# Motors.net
KiCad netlist of a schematic drawn in Altium Designer
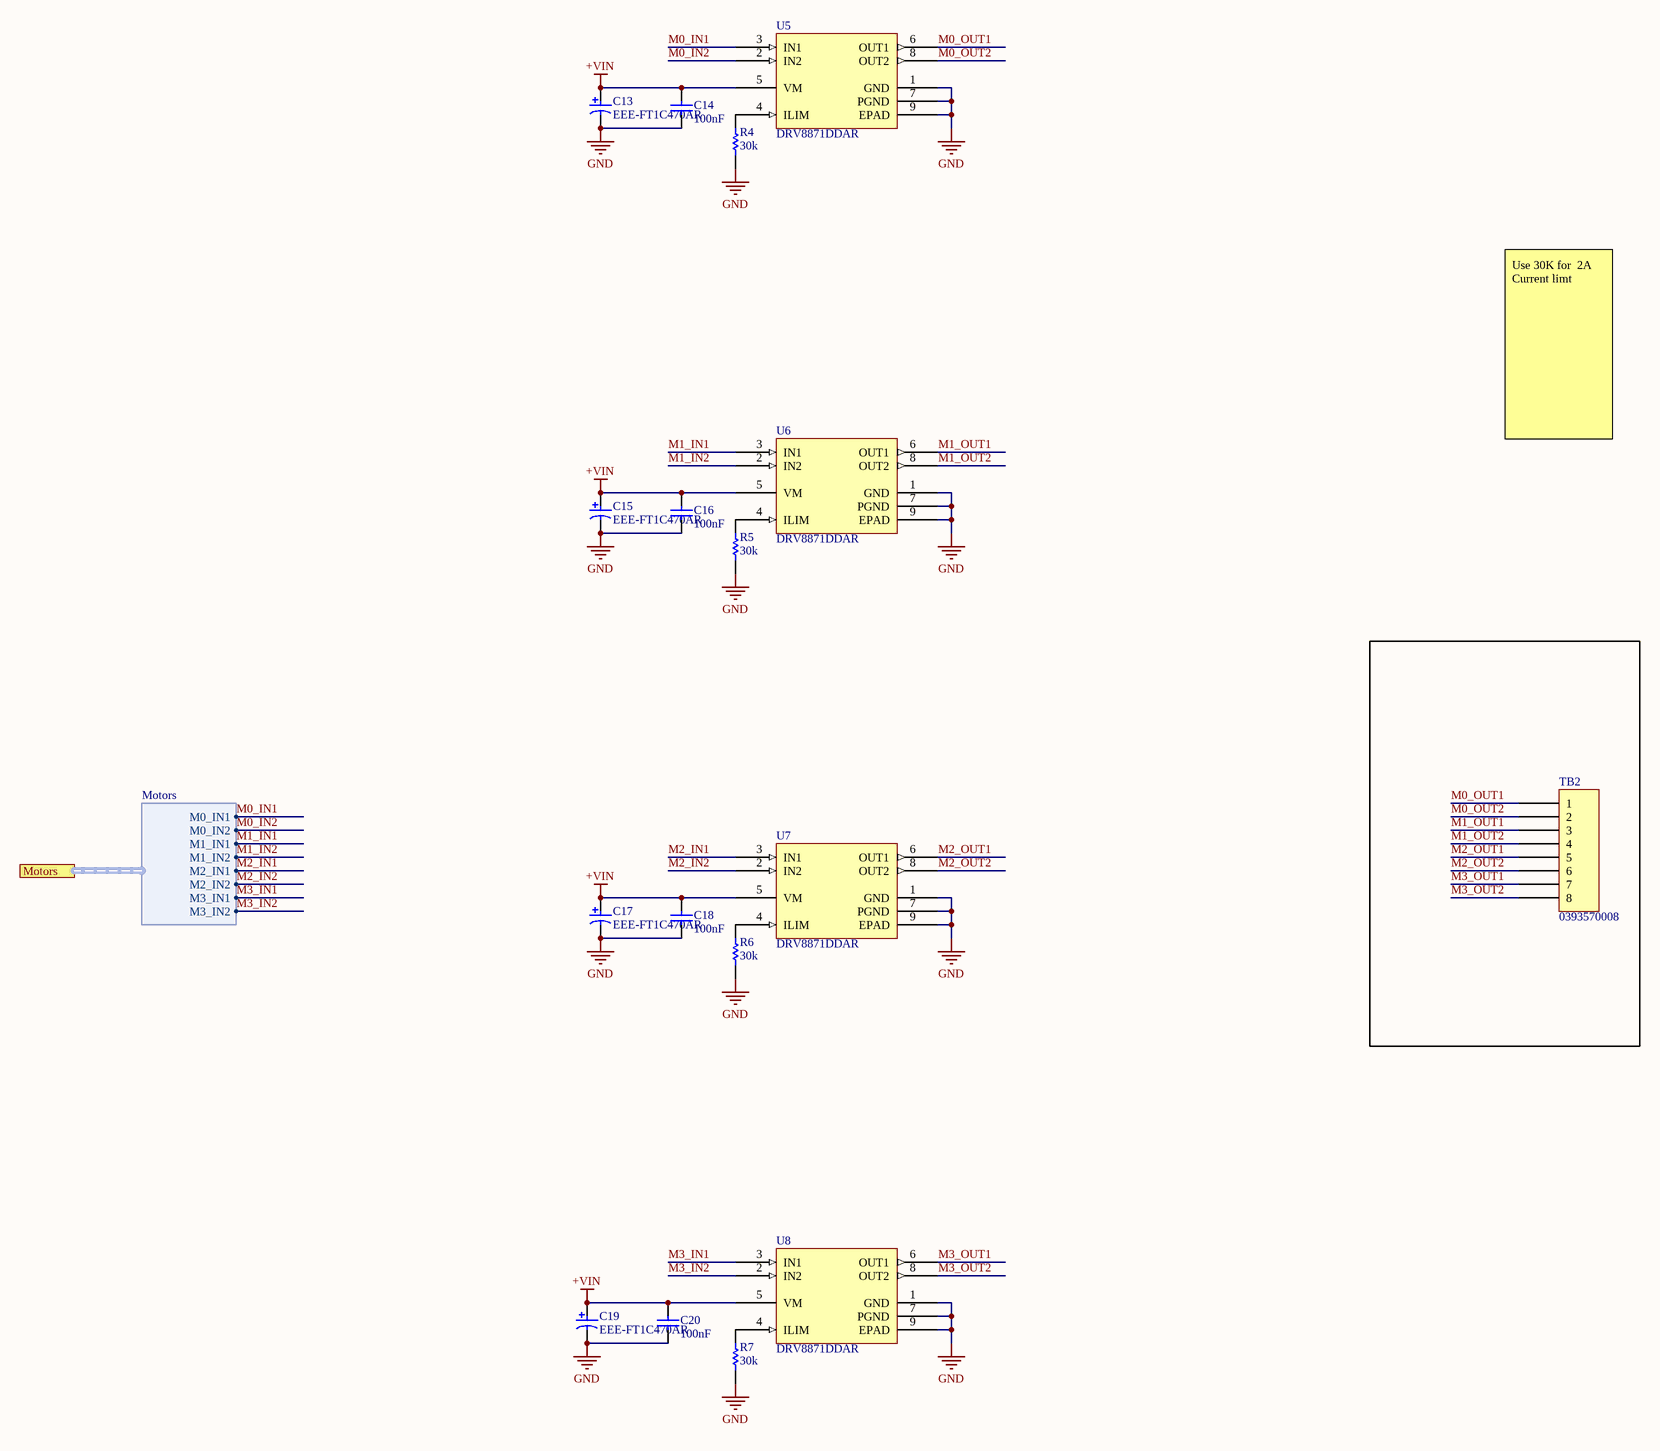
[diagram p0: Motors.SchDoc]

(export (version "E")
  (design (tool "Eeschema 10.0.6"))
  (components
    (comp (ref "C13")
      (value "EEE-FT1C470AR")
      (footprint "EEE-FT1C470AR")
      (fields
        (field (name "MANUFACTURER") "Panasonic")
        (field (name "MANUFACTURER PART NUMBER") "EEEFT1C470AR")
        (field (name "VOLTAGE") "16V")
      )
      (libsource (lib "altium-library") (part "EEE-FT1C470AR"))
    )
    (comp (ref "C14")
      (value "100nF")
      (footprint "0402")
      (description "TDK - C1005X7R1C104K050BC. - CERAMIC CAPACITOR, 0.1UF, 16V, X7R, 10%, 0402, FULL REEL")
      (fields
        (field (name "MANUFACTURER") "TDK")
        (field (name "MANUFACTURER PART NUMBER") "C1005X7R1C104K050BC")
      )
      (libsource (lib "altium-library") (part "Capacitor"))
    )
    (comp (ref "C15")
      (value "EEE-FT1C470AR")
      (footprint "EEE-FT1C470AR")
      (fields
        (field (name "MANUFACTURER") "Panasonic")
        (field (name "MANUFACTURER PART NUMBER") "EEEFT1C470AR")
        (field (name "VOLTAGE") "16V")
      )
      (libsource (lib "altium-library") (part "EEE-FT1C470AR"))
    )
    (comp (ref "C16")
      (value "100nF")
      (footprint "0402")
      (description "TDK - C1005X7R1C104K050BC. - CERAMIC CAPACITOR, 0.1UF, 16V, X7R, 10%, 0402, FULL REEL")
      (fields
        (field (name "MANUFACTURER") "TDK")
        (field (name "MANUFACTURER PART NUMBER") "C1005X7R1C104K050BC")
      )
      (libsource (lib "altium-library") (part "Capacitor"))
    )
    (comp (ref "C17")
      (value "EEE-FT1C470AR")
      (footprint "EEE-FT1C470AR")
      (fields
        (field (name "MANUFACTURER") "Panasonic")
        (field (name "MANUFACTURER PART NUMBER") "EEEFT1C470AR")
        (field (name "VOLTAGE") "16V")
      )
      (libsource (lib "altium-library") (part "EEE-FT1C470AR"))
    )
    (comp (ref "C18")
      (value "100nF")
      (footprint "0402")
      (description "TDK - C1005X7R1C104K050BC. - CERAMIC CAPACITOR, 0.1UF, 16V, X7R, 10%, 0402, FULL REEL")
      (fields
        (field (name "MANUFACTURER") "TDK")
        (field (name "MANUFACTURER PART NUMBER") "C1005X7R1C104K050BC")
      )
      (libsource (lib "altium-library") (part "Capacitor"))
    )
    (comp (ref "C19")
      (value "EEE-FT1C470AR")
      (footprint "EEE-FT1C470AR")
      (fields
        (field (name "MANUFACTURER") "Panasonic")
        (field (name "MANUFACTURER PART NUMBER") "EEEFT1C470AR")
        (field (name "VOLTAGE") "16V")
      )
      (libsource (lib "altium-library") (part "EEE-FT1C470AR"))
    )
    (comp (ref "C20")
      (value "100nF")
      (footprint "0402")
      (description "TDK - C1005X7R1C104K050BC. - CERAMIC CAPACITOR, 0.1UF, 16V, X7R, 10%, 0402, FULL REEL")
      (fields
        (field (name "MANUFACTURER") "TDK")
        (field (name "MANUFACTURER PART NUMBER") "C1005X7R1C104K050BC")
      )
      (libsource (lib "altium-library") (part "Capacitor"))
    )
    (comp (ref "R4")
      (value "30k")
      (footprint "0402")
      (description "Res Thick Film 0402 30K Ohm 1% 0.063W(1/16W) ±100ppm/C Molded SMD Automotive Paper T/R")
      (fields
        (field (name "MANUFACTURER") "Vishay")
        (field (name "MANUFACTURER PART NUMBER") "CRCW040230K0FKED")
      )
      (libsource (lib "altium-library") (part "Resistor"))
    )
    (comp (ref "R5")
      (value "30k")
      (footprint "0402")
      (description "Res Thick Film 0402 30K Ohm 1% 0.063W(1/16W) ±100ppm/C Molded SMD Automotive Paper T/R")
      (fields
        (field (name "MANUFACTURER") "Vishay")
        (field (name "MANUFACTURER PART NUMBER") "CRCW040230K0FKED")
      )
      (libsource (lib "altium-library") (part "Resistor"))
    )
    (comp (ref "R6")
      (value "30k")
      (footprint "0402")
      (description "Res Thick Film 0402 30K Ohm 1% 0.063W(1/16W) ±100ppm/C Molded SMD Automotive Paper T/R")
      (fields
        (field (name "MANUFACTURER") "Vishay")
        (field (name "MANUFACTURER PART NUMBER") "CRCW040230K0FKED")
      )
      (libsource (lib "altium-library") (part "Resistor"))
    )
    (comp (ref "R7")
      (value "30k")
      (footprint "0402")
      (description "Res Thick Film 0402 30K Ohm 1% 0.063W(1/16W) ±100ppm/C Molded SMD Automotive Paper T/R")
      (fields
        (field (name "MANUFACTURER") "Vishay")
        (field (name "MANUFACTURER PART NUMBER") "CRCW040230K0FKED")
      )
      (libsource (lib "altium-library") (part "Resistor"))
    )
    (comp (ref "TB2")
      (value "0393570008")
      (footprint "0393570008")
      (description "Conn Eurostyle Block 8 POS 3.5mm Solder ST Thru-Hole 17.5A/Contact")
      (fields (field (name "MANUFACTURER") "Molex") (field (name "VOLTAGE") "300V"))
      (libsource (lib "altium-library") (part "0393570008"))
    )
    (comp (ref "U5")
      (value "DRV8871DDAR")
      (footprint "8-HSOP")
      (description "IC BRUSHED DC MOTOR 8SOIC")
      (fields (field (name "MANUFACTURER") "Texas Instruments"))
      (libsource (lib "altium-library") (part "DRV8871DDAR"))
    )
    (comp (ref "U6")
      (value "DRV8871DDAR")
      (footprint "8-HSOP")
      (description "IC BRUSHED DC MOTOR 8SOIC")
      (fields (field (name "MANUFACTURER") "Texas Instruments"))
      (libsource (lib "altium-library") (part "DRV8871DDAR"))
    )
    (comp (ref "U7")
      (value "DRV8871DDAR")
      (footprint "8-HSOP")
      (description "IC BRUSHED DC MOTOR 8SOIC")
      (fields (field (name "MANUFACTURER") "Texas Instruments"))
      (libsource (lib "altium-library") (part "DRV8871DDAR"))
    )
    (comp (ref "U8")
      (value "DRV8871DDAR")
      (footprint "8-HSOP")
      (description "IC BRUSHED DC MOTOR 8SOIC")
      (fields (field (name "MANUFACTURER") "Texas Instruments"))
      (libsource (lib "altium-library") (part "DRV8871DDAR"))
    )
  )
  (nets
    (net (code "2") (name "+VIN") (class "Default")
      (node (ref "C13") (pin "1") (pinfunction "1_1") (pintype "passive"))
      (node (ref "C14") (pin "2") (pinfunction "2_2") (pintype "passive"))
      (node (ref "C15") (pin "1") (pinfunction "1_1") (pintype "passive"))
      (node (ref "C16") (pin "2") (pinfunction "2_2") (pintype "passive"))
      (node (ref "C17") (pin "1") (pinfunction "1_1") (pintype "passive"))
      (node (ref "C18") (pin "2") (pinfunction "2_2") (pintype "passive"))
      (node (ref "C19") (pin "1") (pinfunction "1_1") (pintype "passive"))
      (node (ref "C20") (pin "2") (pinfunction "2_2") (pintype "passive"))
      (node (ref "U5") (pin "5") (pinfunction "VM_5") (pintype "power_in"))
      (node (ref "U6") (pin "5") (pinfunction "VM_5") (pintype "power_in"))
      (node (ref "U7") (pin "5") (pinfunction "VM_5") (pintype "power_in"))
      (node (ref "U8") (pin "5") (pinfunction "VM_5") (pintype "power_in"))
    )
    (net (code "3") (name "/M0_IN1") (class "Default")
      (node (ref "U5") (pin "3") (pinfunction "IN1_3") (pintype "input"))
    )
    (net (code "4") (name "/M0_IN2") (class "Default")
      (node (ref "U5") (pin "2") (pinfunction "IN2_2") (pintype "input"))
    )
    (net (code "5") (name "/M0_OUT1") (class "Default")
      (node (ref "TB2") (pin "1") (pinfunction "1_1") (pintype "passive"))
      (node (ref "U5") (pin "6") (pinfunction "OUT1_6") (pintype "output"))
    )
    (net (code "6") (name "/M0_OUT2") (class "Default")
      (node (ref "TB2") (pin "2") (pinfunction "2_2") (pintype "passive"))
      (node (ref "U5") (pin "8") (pinfunction "OUT2_8") (pintype "output"))
    )
    (net (code "7") (name "/M1_IN1") (class "Default")
      (node (ref "U6") (pin "3") (pinfunction "IN1_3") (pintype "input"))
    )
    (net (code "8") (name "/M1_IN2") (class "Default")
      (node (ref "U6") (pin "2") (pinfunction "IN2_2") (pintype "input"))
    )
    (net (code "9") (name "/M1_OUT1") (class "Default")
      (node (ref "TB2") (pin "3") (pinfunction "3_3") (pintype "passive"))
      (node (ref "U6") (pin "6") (pinfunction "OUT1_6") (pintype "output"))
    )
    (net (code "10") (name "/M1_OUT2") (class "Default")
      (node (ref "TB2") (pin "4") (pinfunction "4_4") (pintype "passive"))
      (node (ref "U6") (pin "8") (pinfunction "OUT2_8") (pintype "output"))
    )
    (net (code "11") (name "/M2_IN1") (class "Default")
      (node (ref "U7") (pin "3") (pinfunction "IN1_3") (pintype "input"))
    )
    (net (code "12") (name "/M2_IN2") (class "Default")
      (node (ref "U7") (pin "2") (pinfunction "IN2_2") (pintype "input"))
    )
    (net (code "13") (name "/M2_OUT1") (class "Default")
      (node (ref "TB2") (pin "5") (pinfunction "5_5") (pintype "passive"))
      (node (ref "U7") (pin "6") (pinfunction "OUT1_6") (pintype "output"))
    )
    (net (code "14") (name "/M2_OUT2") (class "Default")
      (node (ref "TB2") (pin "6") (pinfunction "6_6") (pintype "passive"))
      (node (ref "U7") (pin "8") (pinfunction "OUT2_8") (pintype "output"))
    )
    (net (code "15") (name "/M3_IN1") (class "Default")
      (node (ref "U8") (pin "3") (pinfunction "IN1_3") (pintype "input"))
    )
    (net (code "16") (name "/M3_IN2") (class "Default")
      (node (ref "U8") (pin "2") (pinfunction "IN2_2") (pintype "input"))
    )
    (net (code "17") (name "/M3_OUT1") (class "Default")
      (node (ref "TB2") (pin "7") (pinfunction "7_7") (pintype "passive"))
      (node (ref "U8") (pin "6") (pinfunction "OUT1_6") (pintype "output"))
    )
    (net (code "18") (name "/M3_OUT2") (class "Default")
      (node (ref "TB2") (pin "8") (pinfunction "8_8") (pintype "passive"))
      (node (ref "U8") (pin "8") (pinfunction "OUT2_8") (pintype "output"))
    )
    (net (code "20") (name "GND") (class "Default")
      (node (ref "C13") (pin "2") (pinfunction "2_2") (pintype "passive"))
      (node (ref "C14") (pin "1") (pinfunction "1_1") (pintype "passive"))
      (node (ref "C15") (pin "2") (pinfunction "2_2") (pintype "passive"))
      (node (ref "C16") (pin "1") (pinfunction "1_1") (pintype "passive"))
      (node (ref "C17") (pin "2") (pinfunction "2_2") (pintype "passive"))
      (node (ref "C18") (pin "1") (pinfunction "1_1") (pintype "passive"))
      (node (ref "C19") (pin "2") (pinfunction "2_2") (pintype "passive"))
      (node (ref "C20") (pin "1") (pinfunction "1_1") (pintype "passive"))
      (node (ref "R4") (pin "1") (pinfunction "1_1") (pintype "passive"))
      (node (ref "R5") (pin "1") (pinfunction "1_1") (pintype "passive"))
      (node (ref "R6") (pin "1") (pinfunction "1_1") (pintype "passive"))
      (node (ref "R7") (pin "1") (pinfunction "1_1") (pintype "passive"))
      (node (ref "U5") (pin "1") (pinfunction "GND_1") (pintype "power_in"))
      (node (ref "U5") (pin "7") (pinfunction "PGND_7") (pintype "power_in"))
      (node (ref "U5") (pin "9") (pinfunction "EPAD_9") (pintype "power_in"))
      (node (ref "U6") (pin "1") (pinfunction "GND_1") (pintype "power_in"))
      (node (ref "U6") (pin "7") (pinfunction "PGND_7") (pintype "power_in"))
      (node (ref "U6") (pin "9") (pinfunction "EPAD_9") (pintype "power_in"))
      (node (ref "U7") (pin "1") (pinfunction "GND_1") (pintype "power_in"))
      (node (ref "U7") (pin "7") (pinfunction "PGND_7") (pintype "power_in"))
      (node (ref "U7") (pin "9") (pinfunction "EPAD_9") (pintype "power_in"))
      (node (ref "U8") (pin "1") (pinfunction "GND_1") (pintype "power_in"))
      (node (ref "U8") (pin "7") (pinfunction "PGND_7") (pintype "power_in"))
      (node (ref "U8") (pin "9") (pinfunction "EPAD_9") (pintype "power_in"))
    )
    (net (code "21") (name "Net-(U5-ILIM)") (class "Default")
      (node (ref "R4") (pin "2") (pinfunction "2_2") (pintype "passive"))
      (node (ref "U5") (pin "4") (pinfunction "ILIM_4") (pintype "input"))
    )
    (net (code "22") (name "Net-(U6-ILIM)") (class "Default")
      (node (ref "R5") (pin "2") (pinfunction "2_2") (pintype "passive"))
      (node (ref "U6") (pin "4") (pinfunction "ILIM_4") (pintype "input"))
    )
    (net (code "23") (name "Net-(U7-ILIM)") (class "Default")
      (node (ref "R6") (pin "2") (pinfunction "2_2") (pintype "passive"))
      (node (ref "U7") (pin "4") (pinfunction "ILIM_4") (pintype "input"))
    )
    (net (code "24") (name "Net-(U8-ILIM)") (class "Default")
      (node (ref "R7") (pin "2") (pinfunction "2_2") (pintype "passive"))
      (node (ref "U8") (pin "4") (pinfunction "ILIM_4") (pintype "input"))
    )
  )
)
